# shinobi_5v_3V3_dcdc.net
KiCad netlist of a schematic drawn in EAGLE
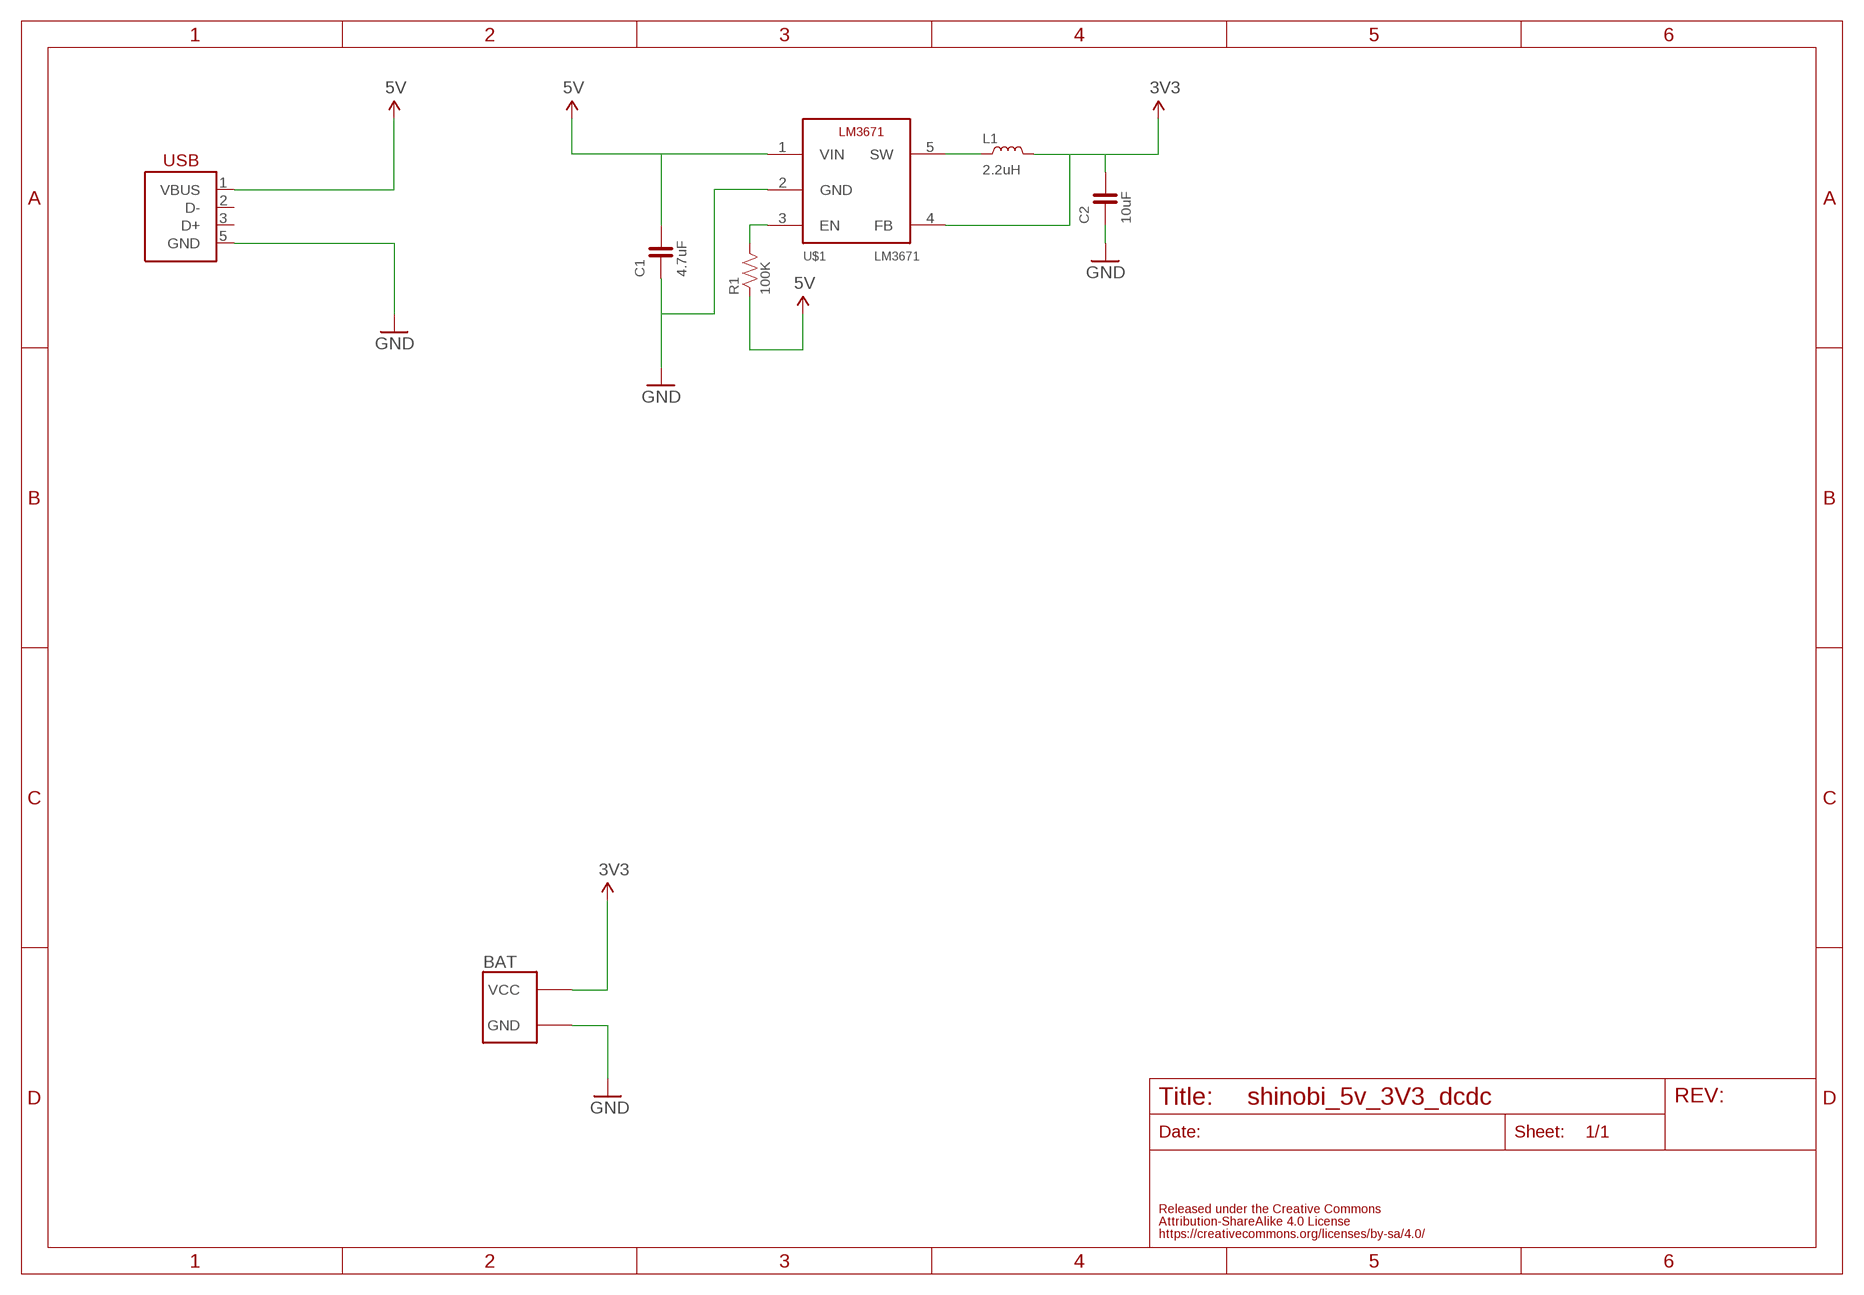
[diagram p0: schematic, sheet 1]

(export (version "E")
  (design (tool "Eeschema 10.0.6"))
  (components
    (comp (ref "BAT")
      (value "FABO_BRICK_2PIN_SIDE")
      (footprint "eagle-import:FABO_BRICK_2PIN_S02B−PASK-2_SILK")
      (libsource (lib "eagle-import") (part "FABO_BRICK_2PIN_SIDE"))
    )
    (comp (ref "C1")
      (value "4.7uF")
      (footprint "eagle-import:0603")
      (libsource (lib "eagle-import") (part "CAPACITOR-0603"))
    )
    (comp (ref "C2")
      (value "10uF")
      (footprint "eagle-import:0603")
      (libsource (lib "eagle-import") (part "CAPACITOR-0603"))
    )
    (comp (ref "L1")
      (value "2.2uH")
      (footprint "eagle-import:2.4X2.4")
      (libsource (lib "eagle-import") (part "INDUCTOR2.4X2.4"))
    )
    (comp (ref "R1")
      (value "100K")
      (footprint "eagle-import:0603")
      (libsource (lib "eagle-import") (part "RESISTOR-0603"))
    )
    (comp (ref "U$1")
      (value "LM3671")
      (footprint "eagle-import:LM3671")
      (libsource (lib "eagle-import") (part "LM3671"))
    )
    (comp (ref "USB1")
      (value "USB-MICRO_B_SMT_HIROSE")
      (footprint "eagle-import:ZX62R-B-5P")
      (libsource (lib "eagle-import") (part "USB-MICRO_B_SMT_HIROSE"))
    )
  )
  (nets
    (net (code "1") (name "3V3") (class "Default")
      (node (ref "BAT") (pin "VCC") (pinfunction "VCC_VCC") (pintype "bidirectional"))
      (node (ref "C2") (pin "2") (pinfunction "2_2") (pintype "passive"))
      (node (ref "L1") (pin "P$2") (pinfunction "2_P$2") (pintype "bidirectional"))
      (node (ref "U$1") (pin "4") (pinfunction "FB_4") (pintype "bidirectional"))
    )
    (net (code "2") (name "5V") (class "Default")
      (node (ref "C1") (pin "2") (pinfunction "2_2") (pintype "passive"))
      (node (ref "R1") (pin "1") (pinfunction "1_1") (pintype "bidirectional"))
      (node (ref "U$1") (pin "1") (pinfunction "VIN_1") (pintype "bidirectional"))
      (node (ref "USB1") (pin "1") (pinfunction "VBUS_1") (pintype "bidirectional"))
    )
    (net (code "3") (name "GND") (class "Default")
      (node (ref "BAT") (pin "GND") (pinfunction "GND_GND") (pintype "bidirectional"))
      (node (ref "C1") (pin "1") (pinfunction "1_1") (pintype "passive"))
      (node (ref "C2") (pin "1") (pinfunction "1_1") (pintype "passive"))
      (node (ref "U$1") (pin "2") (pinfunction "GND_2") (pintype "bidirectional"))
      (node (ref "USB1") (pin "5") (pinfunction "GND_5") (pintype "bidirectional"))
    )
    (net (code "4") (name "Net-(L1-1)") (class "Default")
      (node (ref "L1") (pin "P$1") (pinfunction "1_P$1") (pintype "bidirectional"))
      (node (ref "U$1") (pin "5") (pinfunction "SW_5") (pintype "bidirectional"))
    )
    (net (code "5") (name "Net-(U$1-EN)") (class "Default")
      (node (ref "R1") (pin "2") (pinfunction "2_2") (pintype "bidirectional"))
      (node (ref "U$1") (pin "3") (pinfunction "EN_3") (pintype "bidirectional"))
    )
    (net (code "6") (name "unconnected-(USB1-D+-Pad3)") (class "Default")
      (node (ref "USB1") (pin "3") (pinfunction "D+_3") (pintype "bidirectional"))
    )
    (net (code "7") (name "unconnected-(USB1-D--Pad2)") (class "Default")
      (node (ref "USB1") (pin "2") (pinfunction "D-_2") (pintype "bidirectional"))
    )
  )
)
